# 3_ADST32-Peripherals.net
KiCad netlist of a schematic drawn in Altium Designer
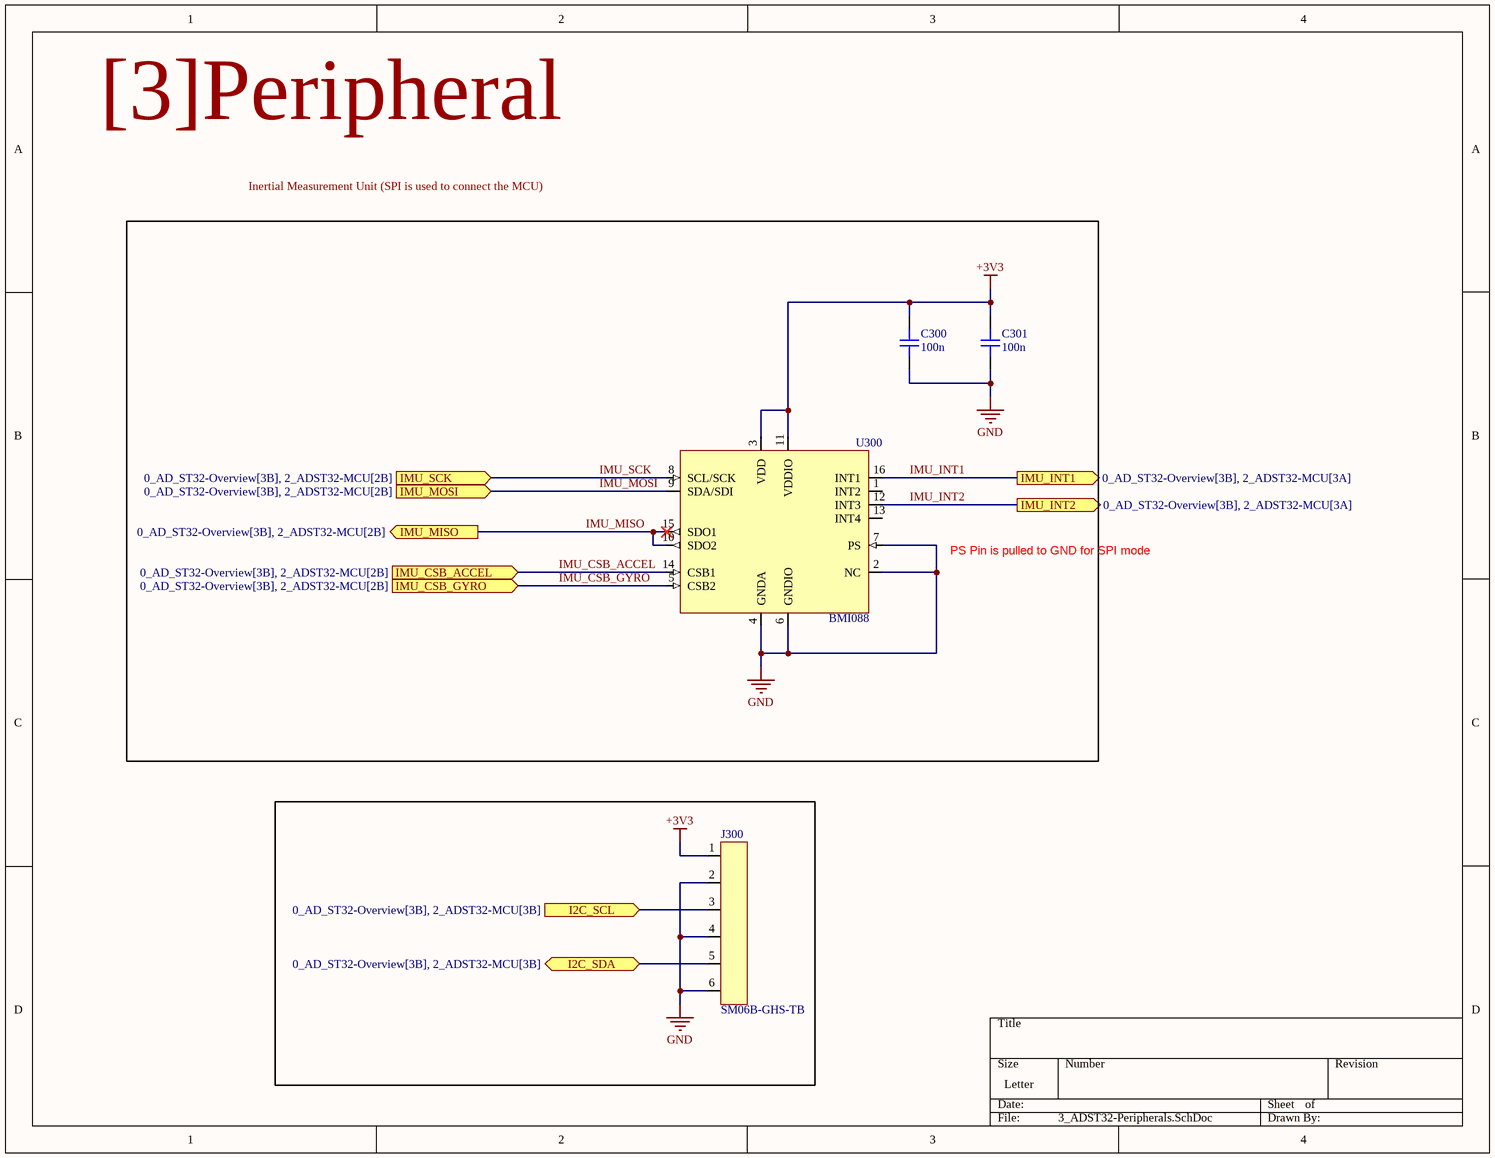
[diagram p0: 3_ADST32-Peripherals.SchDoc]

(export (version "E")
  (design (tool "Eeschema 10.0.6"))
  (components
    (comp (ref "C300")
      (value "100n")
      (footprint "CAP_0603")
      (description "Capacitor SMD 0603")
      (libsource (lib "Schematic-Lib-PhilsLab") (part "CAP_0603"))
    )
    (comp (ref "C301")
      (value "100n")
      (footprint "CAP_0603")
      (description "Capacitor SMD 0603")
      (libsource (lib "Schematic-Lib-PhilsLab") (part "CAP_0603"))
    )
    (comp (ref "J300")
      (value "SM06B-GHS-TB")
      (footprint "SM06B-GHS-TB")
      (description "Header Connector 6 Position 1.25MM Pitch SMD Horizontal JST GH")
      (fields (field (name "MANUFACTURER") "JST"))
      (libsource (lib "Schematic-Lib-PhilsLab") (part "SM06B-GHS-TB"))
    )
    (comp (ref "U300")
      (value "BMI088")
      (footprint "BMI088")
      (description "Inertial Measurement Unit IMU 6-Axis LGA")
      (fields (field (name "MANUFACTURER") "Bosch"))
      (libsource (lib "Schematic-Lib-PhilsLab") (part "BMI088"))
    )
  )
  (nets
    (net (code "1") (name "+3V3") (class "Default")
      (node (ref "C300") (pin "2") (pinfunction "2_2") (pintype "passive"))
      (node (ref "C301") (pin "2") (pinfunction "2_2") (pintype "passive"))
      (node (ref "J300") (pin "1") (pinfunction "1_1") (pintype "passive"))
      (node (ref "U300") (pin "11") (pinfunction "VDDIO_11") (pintype "power_in"))
      (node (ref "U300") (pin "3") (pinfunction "VDD_3") (pintype "power_in"))
    )
    (net (code "2") (name "/I2C_SCL") (class "Default")
      (node (ref "J300") (pin "3") (pinfunction "3_3") (pintype "passive"))
    )
    (net (code "3") (name "/I2C_SDA") (class "Default")
      (node (ref "J300") (pin "5") (pinfunction "5_5") (pintype "passive"))
    )
    (net (code "4") (name "/IMU_CSB_ACCEL") (class "Default")
      (node (ref "U300") (pin "14") (pinfunction "CSB1_14") (pintype "input"))
    )
    (net (code "5") (name "/IMU_CSB_GYRO") (class "Default")
      (node (ref "U300") (pin "5") (pinfunction "CSB2_5") (pintype "input"))
    )
    (net (code "6") (name "/IMU_INT1") (class "Default")
      (node (ref "U300") (pin "16") (pinfunction "INT1_16") (pintype "bidirectional"))
    )
    (net (code "7") (name "/IMU_INT2") (class "Default")
      (node (ref "U300") (pin "12") (pinfunction "INT3_12") (pintype "bidirectional"))
    )
    (net (code "8") (name "/IMU_MISO") (class "Default")
      (node (ref "U300") (pin "10") (pinfunction "SDO2_10") (pintype "output"))
      (node (ref "U300") (pin "15") (pinfunction "SDO1_15") (pintype "output"))
    )
    (net (code "9") (name "/IMU_MOSI") (class "Default")
      (node (ref "U300") (pin "9") (pinfunction "SDA/SDI_9") (pintype "bidirectional"))
    )
    (net (code "10") (name "/IMU_SCK") (class "Default")
      (node (ref "U300") (pin "8") (pinfunction "SCL/SCK_8") (pintype "input"))
    )
    (net (code "11") (name "GND") (class "Default")
      (node (ref "C300") (pin "1") (pinfunction "1_1") (pintype "passive"))
      (node (ref "C301") (pin "1") (pinfunction "1_1") (pintype "passive"))
      (node (ref "J300") (pin "2") (pinfunction "2_2") (pintype "passive"))
      (node (ref "J300") (pin "4") (pinfunction "4_4") (pintype "passive"))
      (node (ref "J300") (pin "6") (pinfunction "6_6") (pintype "passive"))
      (node (ref "U300") (pin "2") (pinfunction "NC_2") (pintype "passive"))
      (node (ref "U300") (pin "4") (pinfunction "GNDA_4") (pintype "power_in"))
      (node (ref "U300") (pin "6") (pinfunction "GNDIO_6") (pintype "power_in"))
      (node (ref "U300") (pin "7") (pinfunction "PS_7") (pintype "input"))
    )
    (net (code "12") (name "unconnected-(U300-INT2-Pad1)") (class "Default")
      (node (ref "U300") (pin "1") (pinfunction "INT2_1") (pintype "bidirectional"))
    )
    (net (code "13") (name "unconnected-(U300-INT4-Pad13)") (class "Default")
      (node (ref "U300") (pin "13") (pinfunction "INT4_13") (pintype "bidirectional"))
    )
  )
)
